# USB.net
KiCad netlist of a schematic drawn in Altium Designer
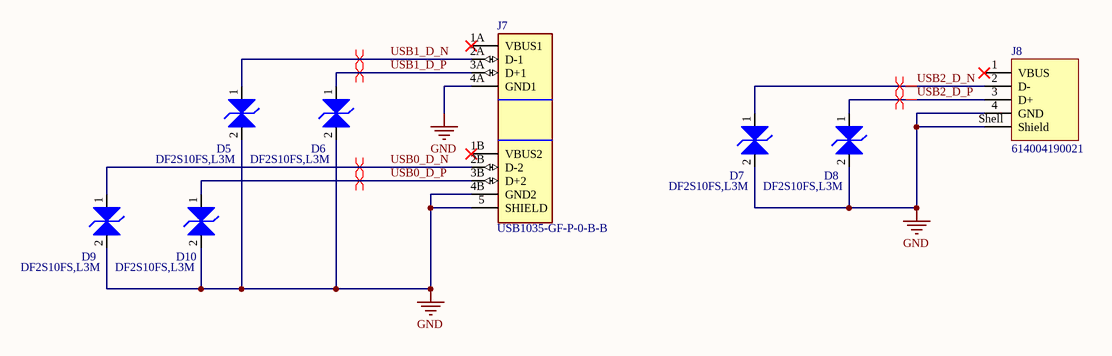
[diagram p0: USB.SchDoc]

(export (version "E")
  (design (tool "Eeschema 10.0.6"))
  (components
    (comp (ref "D5")
      (value "DF2S10FS,L3M")
      (footprint "DF2S10FS,L3M")
      (description "TVS Diode 8VRM")
      (libsource (lib "Master") (part "DF2S10FS,L3M"))
    )
    (comp (ref "D6")
      (value "DF2S10FS,L3M")
      (footprint "DF2S10FS,L3M")
      (description "TVS Diode 8VRM")
      (libsource (lib "Master") (part "DF2S10FS,L3M"))
    )
    (comp (ref "D7")
      (value "DF2S10FS,L3M")
      (footprint "DF2S10FS,L3M")
      (description "TVS Diode 8VRM")
      (libsource (lib "Master") (part "DF2S10FS,L3M"))
    )
    (comp (ref "D8")
      (value "DF2S10FS,L3M")
      (footprint "DF2S10FS,L3M")
      (description "TVS Diode 8VRM")
      (libsource (lib "Master") (part "DF2S10FS,L3M"))
    )
    (comp (ref "D9")
      (value "DF2S10FS,L3M")
      (footprint "DF2S10FS,L3M")
      (description "TVS Diode 8VRM")
      (libsource (lib "Master") (part "DF2S10FS,L3M"))
    )
    (comp (ref "D10")
      (value "DF2S10FS,L3M")
      (footprint "DF2S10FS,L3M")
      (description "TVS Diode 8VRM")
      (libsource (lib "Master") (part "DF2S10FS,L3M"))
    )
    (comp (ref "J7")
      (value "USB1035-GF-P-0-B-B")
      (footprint "USB1035-GF-P-0-B-B")
      (description "USB-A (USB TYPE-A), Stacked USB 2.0 Receptacle Connector 8 Position Through Hole, Right Angle")
      (fields (field (name "MF") "Global Connector Technology"))
      (libsource (lib "Master") (part "USB1035-GF-P-0-B-B"))
    )
    (comp (ref "J8")
      (value "614004190021")
      (footprint "614004190021")
      (libsource (lib "Altium Content Vault") (part "USB 2.0_Type A_Receptacle_1 Port"))
    )
  )
  (nets
    (net (code "1") (name "/USB0_D_N") (class "Default")
      (node (ref "D9") (pin "1") (pintype "passive"))
      (node (ref "J7") (pin "2B") (pinfunction "D-2_2B") (pintype "bidirectional"))
    )
    (net (code "2") (name "/USB0_D_P") (class "Default")
      (node (ref "D10") (pin "1") (pintype "passive"))
      (node (ref "J7") (pin "3B") (pinfunction "D+2_3B") (pintype "bidirectional"))
    )
    (net (code "3") (name "/USB1_D_N") (class "Default")
      (node (ref "D5") (pin "1") (pintype "passive"))
      (node (ref "J7") (pin "2A") (pinfunction "D-1_2A") (pintype "bidirectional"))
    )
    (net (code "4") (name "/USB1_D_P") (class "Default")
      (node (ref "D6") (pin "1") (pintype "passive"))
      (node (ref "J7") (pin "3A") (pinfunction "D+1_3A") (pintype "bidirectional"))
    )
    (net (code "5") (name "/USB2_D_N") (class "Default")
      (node (ref "D7") (pin "1") (pintype "passive"))
      (node (ref "J8") (pin "2") (pinfunction "D-_2") (pintype "passive"))
    )
    (net (code "6") (name "/USB2_D_P") (class "Default")
      (node (ref "D8") (pin "1") (pintype "passive"))
      (node (ref "J8") (pin "3") (pinfunction "D+_3") (pintype "passive"))
    )
    (net (code "7") (name "GND") (class "Default")
      (node (ref "D10") (pin "2") (pintype "passive"))
      (node (ref "D5") (pin "2") (pintype "passive"))
      (node (ref "D6") (pin "2") (pintype "passive"))
      (node (ref "D7") (pin "2") (pintype "passive"))
      (node (ref "D8") (pin "2") (pintype "passive"))
      (node (ref "D9") (pin "2") (pintype "passive"))
      (node (ref "J7") (pin "4A") (pinfunction "GND1_4A") (pintype "power_in"))
      (node (ref "J7") (pin "4B") (pinfunction "GND2_4B") (pintype "power_in"))
      (node (ref "J7") (pin "5") (pinfunction "SHIELD_5") (pintype "power_in"))
      (node (ref "J8") (pin "4") (pinfunction "GND_4") (pintype "passive"))
      (node (ref "J8") (pin "Shell") (pinfunction "Shield_Shell") (pintype "passive"))
    )
    (net (code "8") (name "unconnected-(J7-VBUS1-Pad1A)") (class "Default")
      (node (ref "J7") (pin "1A") (pinfunction "VBUS1_1A") (pintype "power_in+no_connect"))
    )
    (net (code "9") (name "unconnected-(J7-VBUS2-Pad1B)") (class "Default")
      (node (ref "J7") (pin "1B") (pinfunction "VBUS2_1B") (pintype "power_in+no_connect"))
    )
    (net (code "10") (name "unconnected-(J8-VBUS-Pad1)") (class "Default")
      (node (ref "J8") (pin "1") (pinfunction "VBUS_1") (pintype "passive+no_connect"))
    )
  )
)
